# Grove-Base_Shield_v1_3.net
KiCad netlist of a schematic drawn in EAGLE
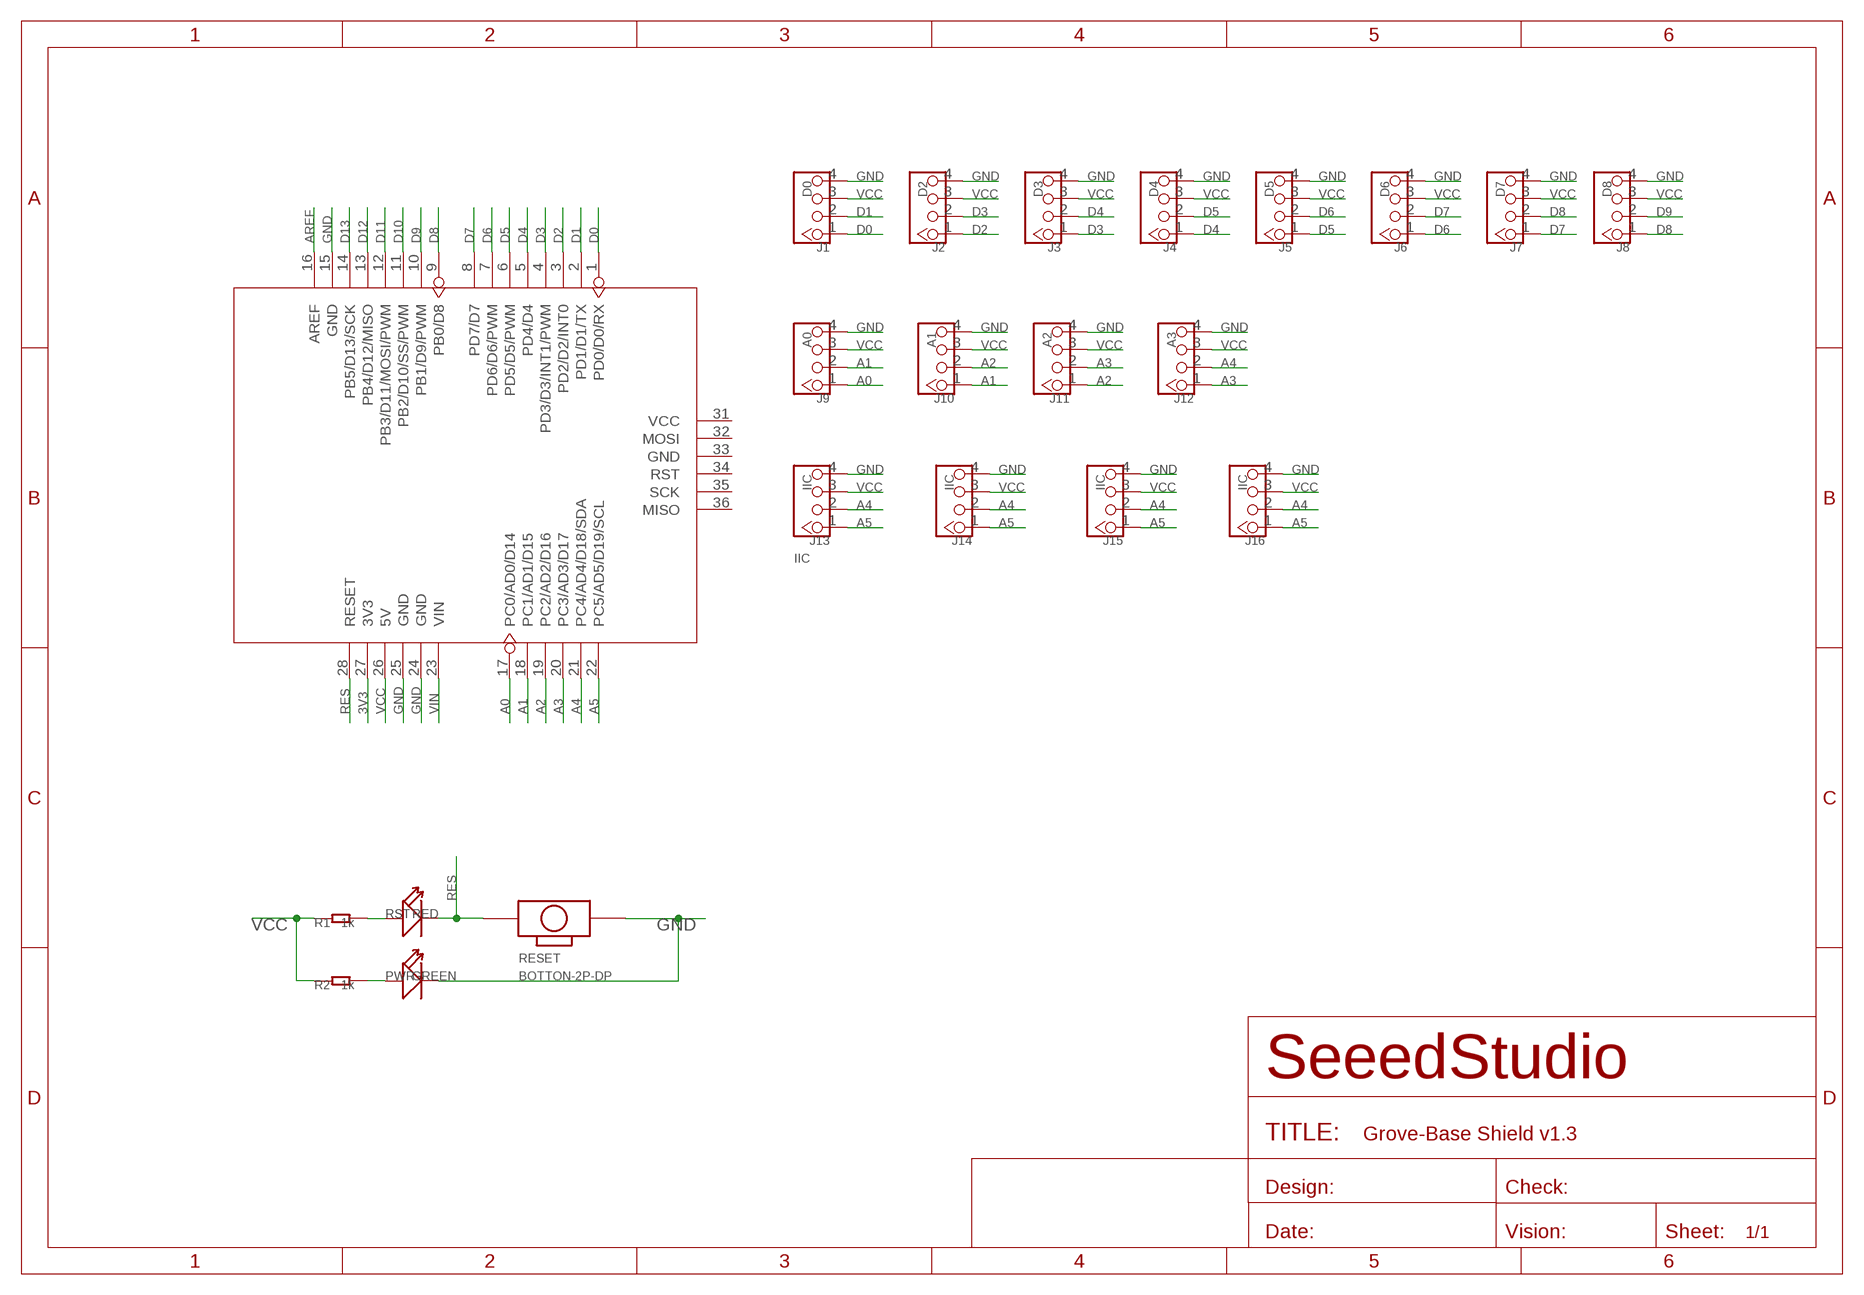
[diagram p0: schematic, sheet 1]

(export (version "E")
  (design (tool "Eeschema 10.0.6"))
  (components
    (comp (ref "J1")
      (value "D0")
      (footprint "eagle-import:4P-2.0")
      (libsource (lib "eagle-import") (part "TWIG-4P-2.0-2.0"))
    )
    (comp (ref "J2")
      (value "D2")
      (footprint "eagle-import:4P-2.0")
      (libsource (lib "eagle-import") (part "TWIG-4P-2.0-2.0"))
    )
    (comp (ref "J3")
      (value "D3")
      (footprint "eagle-import:4P-2.0")
      (libsource (lib "eagle-import") (part "TWIG-4P-2.0-2.0"))
    )
    (comp (ref "J4")
      (value "D4")
      (footprint "eagle-import:4P-2.0")
      (libsource (lib "eagle-import") (part "TWIG-4P-2.0-2.0"))
    )
    (comp (ref "J5")
      (value "D5")
      (footprint "eagle-import:4P-2.0")
      (libsource (lib "eagle-import") (part "TWIG-4P-2.0-2.0"))
    )
    (comp (ref "J6")
      (value "D6")
      (footprint "eagle-import:4P-2.0")
      (libsource (lib "eagle-import") (part "TWIG-4P-2.0-2.0"))
    )
    (comp (ref "J7")
      (value "D7")
      (footprint "eagle-import:4P-2.0")
      (libsource (lib "eagle-import") (part "TWIG-4P-2.0-2.0"))
    )
    (comp (ref "J8")
      (value "D8")
      (footprint "eagle-import:4P-2.0")
      (libsource (lib "eagle-import") (part "TWIG-4P-2.0-2.0"))
    )
    (comp (ref "J9")
      (value "A0")
      (footprint "eagle-import:4P-2.0-90D")
      (libsource (lib "eagle-import") (part "TWIG-4P-2.0'90D'"))
    )
    (comp (ref "J10")
      (value "A1")
      (footprint "eagle-import:4P-2.0-90D")
      (libsource (lib "eagle-import") (part "TWIG-4P-2.0'90D'"))
    )
    (comp (ref "J11")
      (value "A2")
      (footprint "eagle-import:4P-2.0-90D")
      (libsource (lib "eagle-import") (part "TWIG-4P-2.0'90D'"))
    )
    (comp (ref "J12")
      (value "A3")
      (footprint "eagle-import:4P-2.0-90D")
      (libsource (lib "eagle-import") (part "TWIG-4P-2.0'90D'"))
    )
    (comp (ref "J13")
      (value "IIC")
      (footprint "eagle-import:4P-2.0")
      (libsource (lib "eagle-import") (part "TWIG-4P-2.0-2.0"))
    )
    (comp (ref "J14")
      (value "IIC")
      (footprint "eagle-import:4P-2.0")
      (libsource (lib "eagle-import") (part "TWIG-4P-2.0-2.0"))
    )
    (comp (ref "J15")
      (value "IIC")
      (footprint "eagle-import:4P-2.0")
      (libsource (lib "eagle-import") (part "TWIG-4P-2.0-2.0"))
    )
    (comp (ref "J16")
      (value "IIC")
      (footprint "eagle-import:4P-2.0")
      (libsource (lib "eagle-import") (part "TWIG-4P-2.0-2.0"))
    )
    (comp (ref "PWR")
      (value "GREEN")
      (footprint "eagle-import:LED-2P-2.54-3MM")
      (libsource (lib "eagle-import") (part "LED-3MM"))
    )
    (comp (ref "R1")
      (value "1k")
      (footprint "eagle-import:R0204_7")
      (libsource (lib "eagle-import") (part "R-0204/7"))
    )
    (comp (ref "R2")
      (value "1k")
      (footprint "eagle-import:R0204_7")
      (libsource (lib "eagle-import") (part "R-0204/7"))
    )
    (comp (ref "RESET")
      (value "BOTTON-2P-DP")
      (footprint "eagle-import:2P-7.62X3.56-90D")
      (libsource (lib "eagle-import") (part "BOTTON-2P-90"))
    )
    (comp (ref "RST")
      (value "RED")
      (footprint "eagle-import:LED-2P-2.54-3MM")
      (libsource (lib "eagle-import") (part "LED-3MM"))
    )
    (comp (ref "U1")
      (value "ARDUINO'W/O-SILK'")
      (footprint "eagle-import:ARDUINO-W_O-SILK")
      (libsource (lib "eagle-import") (part "ARDUINO'W/O-SILK'"))
    )
  )
  (nets
    (net (code "1") (name "/3V3") (class "Default")
      (node (ref "U1") (pin "27") (pinfunction "3V3_27") (pintype "bidirectional"))
    )
    (net (code "2") (name "/A0") (class "Default")
      (node (ref "J9") (pin "1") (pinfunction "1_1") (pintype "bidirectional"))
      (node (ref "U1") (pin "17") (pinfunction "PC0/AD0/D14_17") (pintype "bidirectional"))
    )
    (net (code "3") (name "/A1") (class "Default")
      (node (ref "J10") (pin "1") (pinfunction "1_1") (pintype "bidirectional"))
      (node (ref "J9") (pin "2") (pinfunction "2_2") (pintype "bidirectional"))
      (node (ref "U1") (pin "18") (pinfunction "PC1/AD1/D15_18") (pintype "bidirectional"))
    )
    (net (code "4") (name "/A2") (class "Default")
      (node (ref "J10") (pin "2") (pinfunction "2_2") (pintype "bidirectional"))
      (node (ref "J11") (pin "1") (pinfunction "1_1") (pintype "bidirectional"))
      (node (ref "U1") (pin "19") (pinfunction "PC2/AD2/D16_19") (pintype "bidirectional"))
    )
    (net (code "5") (name "/A3") (class "Default")
      (node (ref "J11") (pin "2") (pinfunction "2_2") (pintype "bidirectional"))
      (node (ref "J12") (pin "1") (pinfunction "1_1") (pintype "bidirectional"))
      (node (ref "U1") (pin "20") (pinfunction "PC3/AD3/D17_20") (pintype "bidirectional"))
    )
    (net (code "6") (name "/A4") (class "Default")
      (node (ref "J12") (pin "2") (pinfunction "2_2") (pintype "bidirectional"))
      (node (ref "J13") (pin "2") (pinfunction "2_2") (pintype "bidirectional"))
      (node (ref "J14") (pin "2") (pinfunction "2_2") (pintype "bidirectional"))
      (node (ref "J15") (pin "2") (pinfunction "2_2") (pintype "bidirectional"))
      (node (ref "J16") (pin "2") (pinfunction "2_2") (pintype "bidirectional"))
      (node (ref "U1") (pin "21") (pinfunction "PC4/AD4/D18/SDA_21") (pintype "bidirectional"))
    )
    (net (code "7") (name "/A5") (class "Default")
      (node (ref "J13") (pin "1") (pinfunction "1_1") (pintype "bidirectional"))
      (node (ref "J14") (pin "1") (pinfunction "1_1") (pintype "bidirectional"))
      (node (ref "J15") (pin "1") (pinfunction "1_1") (pintype "bidirectional"))
      (node (ref "J16") (pin "1") (pinfunction "1_1") (pintype "bidirectional"))
      (node (ref "U1") (pin "22") (pinfunction "PC5/AD5/D19/SCL_22") (pintype "bidirectional"))
    )
    (net (code "8") (name "/AREF") (class "Default")
      (node (ref "U1") (pin "16") (pinfunction "AREF_16") (pintype "bidirectional"))
    )
    (net (code "9") (name "/D0") (class "Default")
      (node (ref "J1") (pin "1") (pinfunction "1_1") (pintype "bidirectional"))
      (node (ref "U1") (pin "1") (pinfunction "PD0/D0/RX_1") (pintype "bidirectional"))
    )
    (net (code "10") (name "/D1") (class "Default")
      (node (ref "J1") (pin "2") (pinfunction "2_2") (pintype "bidirectional"))
      (node (ref "U1") (pin "2") (pinfunction "PD1/D1/TX_2") (pintype "bidirectional"))
    )
    (net (code "11") (name "/D2") (class "Default")
      (node (ref "J2") (pin "1") (pinfunction "1_1") (pintype "bidirectional"))
      (node (ref "U1") (pin "3") (pinfunction "PD2/D2/INT0_3") (pintype "bidirectional"))
    )
    (net (code "12") (name "/D3") (class "Default")
      (node (ref "J2") (pin "2") (pinfunction "2_2") (pintype "bidirectional"))
      (node (ref "J3") (pin "1") (pinfunction "1_1") (pintype "bidirectional"))
      (node (ref "U1") (pin "4") (pinfunction "PD3/D3/INT1/PWM_4") (pintype "bidirectional"))
    )
    (net (code "13") (name "/D4") (class "Default")
      (node (ref "J3") (pin "2") (pinfunction "2_2") (pintype "bidirectional"))
      (node (ref "J4") (pin "1") (pinfunction "1_1") (pintype "bidirectional"))
      (node (ref "U1") (pin "5") (pinfunction "PD4/D4_5") (pintype "bidirectional"))
    )
    (net (code "14") (name "/D5") (class "Default")
      (node (ref "J4") (pin "2") (pinfunction "2_2") (pintype "bidirectional"))
      (node (ref "J5") (pin "1") (pinfunction "1_1") (pintype "bidirectional"))
      (node (ref "U1") (pin "6") (pinfunction "PD5/D5/PWM_6") (pintype "bidirectional"))
    )
    (net (code "15") (name "/D6") (class "Default")
      (node (ref "J5") (pin "2") (pinfunction "2_2") (pintype "bidirectional"))
      (node (ref "J6") (pin "1") (pinfunction "1_1") (pintype "bidirectional"))
      (node (ref "U1") (pin "7") (pinfunction "PD6/D6/PWM_7") (pintype "bidirectional"))
    )
    (net (code "16") (name "/D7") (class "Default")
      (node (ref "J6") (pin "2") (pinfunction "2_2") (pintype "bidirectional"))
      (node (ref "J7") (pin "1") (pinfunction "1_1") (pintype "bidirectional"))
      (node (ref "U1") (pin "8") (pinfunction "PD7/D7_8") (pintype "bidirectional"))
    )
    (net (code "17") (name "/D8") (class "Default")
      (node (ref "J7") (pin "2") (pinfunction "2_2") (pintype "bidirectional"))
      (node (ref "J8") (pin "1") (pinfunction "1_1") (pintype "bidirectional"))
      (node (ref "U1") (pin "9") (pinfunction "PB0/D8_9") (pintype "bidirectional"))
    )
    (net (code "18") (name "/D9") (class "Default")
      (node (ref "J8") (pin "2") (pinfunction "2_2") (pintype "bidirectional"))
      (node (ref "U1") (pin "10") (pinfunction "PB1/D9/PWM_10") (pintype "bidirectional"))
    )
    (net (code "19") (name "/D10") (class "Default")
      (node (ref "U1") (pin "11") (pinfunction "PB2/D10/SS/PWM_11") (pintype "bidirectional"))
    )
    (net (code "20") (name "/D11") (class "Default")
      (node (ref "U1") (pin "12") (pinfunction "PB3/D11/MOSI/PWM_12") (pintype "bidirectional"))
    )
    (net (code "21") (name "/D12") (class "Default")
      (node (ref "U1") (pin "13") (pinfunction "PB4/D12/MISO_13") (pintype "bidirectional"))
    )
    (net (code "22") (name "/D13") (class "Default")
      (node (ref "U1") (pin "14") (pinfunction "PB5/D13/SCK_14") (pintype "bidirectional"))
    )
    (net (code "23") (name "/GND") (class "Default")
      (node (ref "J1") (pin "4") (pinfunction "4_4") (pintype "bidirectional"))
      (node (ref "J10") (pin "4") (pinfunction "4_4") (pintype "bidirectional"))
      (node (ref "J11") (pin "4") (pinfunction "4_4") (pintype "bidirectional"))
      (node (ref "J12") (pin "4") (pinfunction "4_4") (pintype "bidirectional"))
      (node (ref "J13") (pin "4") (pinfunction "4_4") (pintype "bidirectional"))
      (node (ref "J14") (pin "4") (pinfunction "4_4") (pintype "bidirectional"))
      (node (ref "J15") (pin "4") (pinfunction "4_4") (pintype "bidirectional"))
      (node (ref "J16") (pin "4") (pinfunction "4_4") (pintype "bidirectional"))
      (node (ref "J2") (pin "4") (pinfunction "4_4") (pintype "bidirectional"))
      (node (ref "J3") (pin "4") (pinfunction "4_4") (pintype "bidirectional"))
      (node (ref "J4") (pin "4") (pinfunction "4_4") (pintype "bidirectional"))
      (node (ref "J5") (pin "4") (pinfunction "4_4") (pintype "bidirectional"))
      (node (ref "J6") (pin "4") (pinfunction "4_4") (pintype "bidirectional"))
      (node (ref "J7") (pin "4") (pinfunction "4_4") (pintype "bidirectional"))
      (node (ref "J8") (pin "4") (pinfunction "4_4") (pintype "bidirectional"))
      (node (ref "J9") (pin "4") (pinfunction "4_4") (pintype "bidirectional"))
      (node (ref "PWR") (pin "K") (pinfunction "-_K") (pintype "passive"))
      (node (ref "RESET") (pin "P$2") (pinfunction "2_P$2") (pintype "bidirectional"))
      (node (ref "U1") (pin "15") (pinfunction "GND_15") (pintype "bidirectional"))
      (node (ref "U1") (pin "24") (pinfunction "GND_24") (pintype "bidirectional"))
      (node (ref "U1") (pin "25") (pinfunction "GND_25") (pintype "bidirectional"))
    )
    (net (code "24") (name "/RES") (class "Default")
      (node (ref "RESET") (pin "P$1") (pinfunction "1_P$1") (pintype "bidirectional"))
      (node (ref "RST") (pin "K") (pinfunction "-_K") (pintype "passive"))
      (node (ref "U1") (pin "28") (pinfunction "RESET_28") (pintype "bidirectional"))
    )
    (net (code "25") (name "/VCC") (class "Default")
      (node (ref "J1") (pin "3") (pinfunction "3_3") (pintype "bidirectional"))
      (node (ref "J10") (pin "3") (pinfunction "3_3") (pintype "bidirectional"))
      (node (ref "J11") (pin "3") (pinfunction "3_3") (pintype "bidirectional"))
      (node (ref "J12") (pin "3") (pinfunction "3_3") (pintype "bidirectional"))
      (node (ref "J13") (pin "3") (pinfunction "3_3") (pintype "bidirectional"))
      (node (ref "J14") (pin "3") (pinfunction "3_3") (pintype "bidirectional"))
      (node (ref "J15") (pin "3") (pinfunction "3_3") (pintype "bidirectional"))
      (node (ref "J16") (pin "3") (pinfunction "3_3") (pintype "bidirectional"))
      (node (ref "J2") (pin "3") (pinfunction "3_3") (pintype "bidirectional"))
      (node (ref "J3") (pin "3") (pinfunction "3_3") (pintype "bidirectional"))
      (node (ref "J4") (pin "3") (pinfunction "3_3") (pintype "bidirectional"))
      (node (ref "J5") (pin "3") (pinfunction "3_3") (pintype "bidirectional"))
      (node (ref "J6") (pin "3") (pinfunction "3_3") (pintype "bidirectional"))
      (node (ref "J7") (pin "3") (pinfunction "3_3") (pintype "bidirectional"))
      (node (ref "J8") (pin "3") (pinfunction "3_3") (pintype "bidirectional"))
      (node (ref "J9") (pin "3") (pinfunction "3_3") (pintype "bidirectional"))
      (node (ref "R1") (pin "1") (pinfunction "1_1") (pintype "passive"))
      (node (ref "R2") (pin "1") (pinfunction "1_1") (pintype "passive"))
      (node (ref "U1") (pin "26") (pinfunction "5V_26") (pintype "bidirectional"))
    )
    (net (code "26") (name "/VIN") (class "Default")
      (node (ref "U1") (pin "23") (pinfunction "VIN_23") (pintype "bidirectional"))
    )
    (net (code "27") (name "Net-(PWR-+)") (class "Default")
      (node (ref "PWR") (pin "A") (pinfunction "+_A") (pintype "passive"))
      (node (ref "R2") (pin "2") (pinfunction "2_2") (pintype "passive"))
    )
    (net (code "28") (name "Net-(RST-+)") (class "Default")
      (node (ref "R1") (pin "2") (pinfunction "2_2") (pintype "passive"))
      (node (ref "RST") (pin "A") (pinfunction "+_A") (pintype "passive"))
    )
    (net (code "29") (name "unconnected-(U1-GND-Pad33)") (class "Default")
      (node (ref "U1") (pin "33") (pinfunction "GND_33") (pintype "bidirectional"))
    )
    (net (code "30") (name "unconnected-(U1-MISO-Pad36)") (class "Default")
      (node (ref "U1") (pin "36") (pinfunction "MISO_36") (pintype "bidirectional"))
    )
    (net (code "31") (name "unconnected-(U1-MOSI-Pad32)") (class "Default")
      (node (ref "U1") (pin "32") (pinfunction "MOSI_32") (pintype "bidirectional"))
    )
    (net (code "32") (name "unconnected-(U1-RST-Pad34)") (class "Default")
      (node (ref "U1") (pin "34") (pinfunction "RST_34") (pintype "bidirectional"))
    )
    (net (code "33") (name "unconnected-(U1-SCK-Pad35)") (class "Default")
      (node (ref "U1") (pin "35") (pinfunction "SCK_35") (pintype "bidirectional"))
    )
    (net (code "34") (name "unconnected-(U1-VCC-Pad31)") (class "Default")
      (node (ref "U1") (pin "31") (pinfunction "VCC_31") (pintype "bidirectional"))
    )
  )
)
